# Pressure_Transducer.net
KiCad netlist of a schematic drawn in Altium Designer
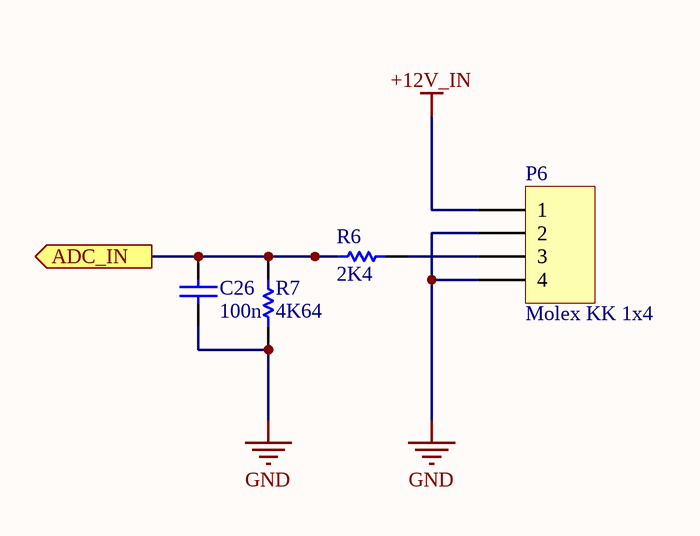
[diagram p0: Pressure_Transducer.SchDoc]

(export (version "E")
  (design (tool "Eeschema 10.0.6"))
  (components
    (comp (ref "C26")
      (value "100n")
      (footprint "C0805")
      (description "0805 Capacitor")
      (libsource (lib "PARSEC1") (part "C0805"))
    )
    (comp (ref "P6")
      (value "Molex KK 1x4")
      (footprint "Molex KK 4x1")
      (description "1x4 Molex KK Connector")
      (libsource (lib "PARSEC") (part "Molex KK 1x4"))
    )
    (comp (ref "R6")
      (value "2K4")
      (footprint "R0805")
      (description "RESISTOR 0805")
      (libsource (lib "PARSEC") (part "R0805"))
    )
    (comp (ref "R7")
      (value "4K64")
      (footprint "R0805")
      (description "RESISTOR 0805")
      (libsource (lib "PARSEC") (part "R0805"))
    )
  )
  (nets
    (net (code "1") (name "+12V_IN") (class "Default")
      (node (ref "P6") (pin "1") (pinfunction "1_1") (pintype "passive"))
    )
    (net (code "2") (name "/ADC_IN") (class "Default")
      (node (ref "C26") (pin "1") (pinfunction "1_1") (pintype "passive"))
      (node (ref "R6") (pin "2") (pinfunction "2_2") (pintype "passive"))
      (node (ref "R7") (pin "2") (pinfunction "2_2") (pintype "passive"))
    )
    (net (code "3") (name "GND") (class "Default")
      (node (ref "C26") (pin "2") (pinfunction "2_2") (pintype "passive"))
      (node (ref "P6") (pin "2") (pinfunction "2_2") (pintype "passive"))
      (node (ref "P6") (pin "4") (pinfunction "4_4") (pintype "passive"))
      (node (ref "R7") (pin "1") (pinfunction "1_1") (pintype "passive"))
    )
    (net (code "4") (name "Net-(P6-Pad3)") (class "Default")
      (node (ref "P6") (pin "3") (pinfunction "3_3") (pintype "passive"))
      (node (ref "R6") (pin "1") (pinfunction "1_1") (pintype "passive"))
    )
  )
)
